# untitled.net
KiCad netlist of a schematic drawn in EAGLE
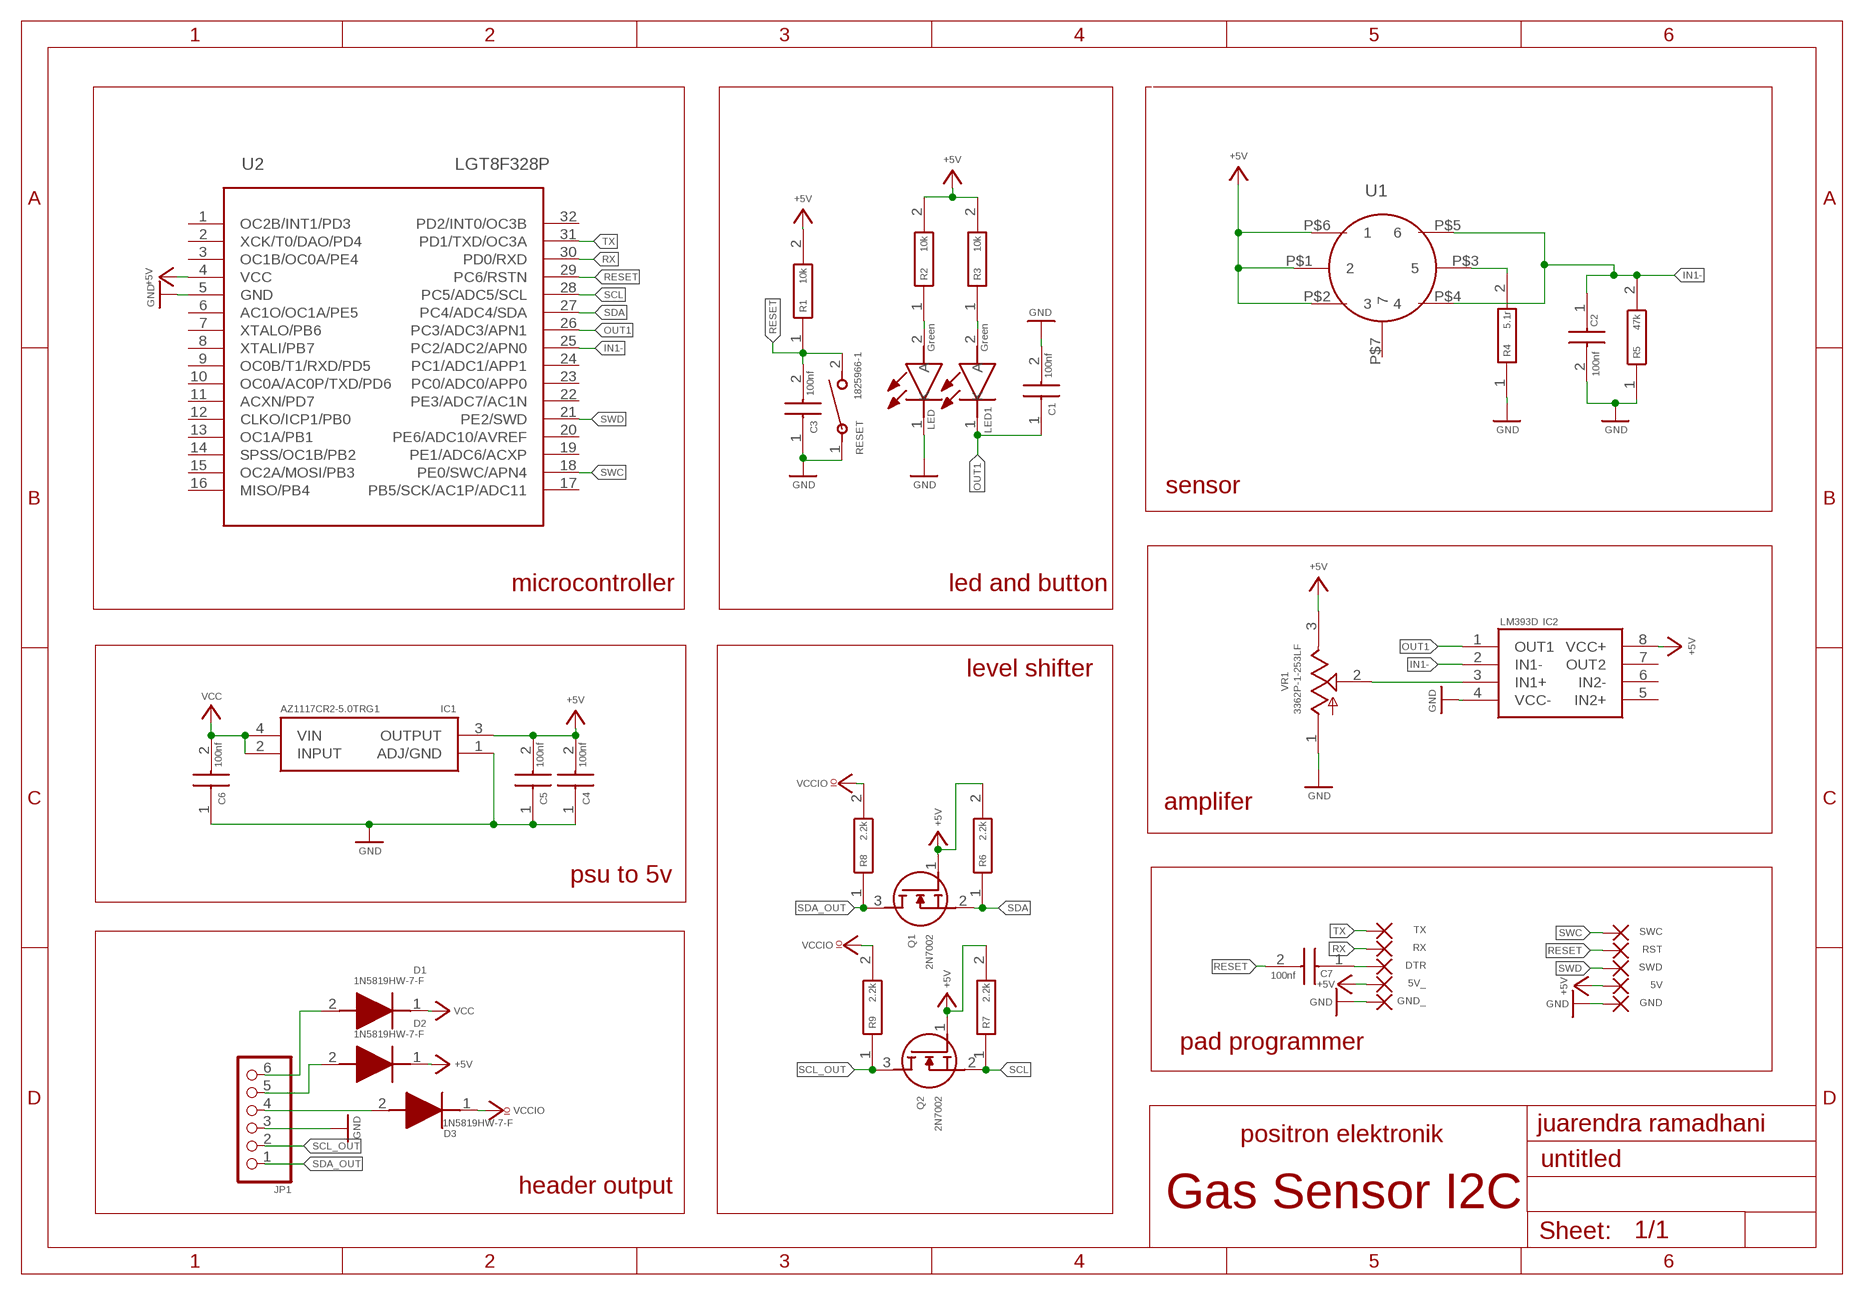
[diagram p0: schematic, sheet 1]

(export (version "E")
  (design (tool "Eeschema 10.0.6"))
  (components
    (comp (ref "5V")
      (value "SMD2")
      (footprint "eagle-import:SMD1,27-2,54")
      (libsource (lib "eagle-import") (part "SMD2"))
    )
    (comp (ref "5V_")
      (value "SMD2")
      (footprint "eagle-import:SMD1,27-2,54")
      (libsource (lib "eagle-import") (part "SMD2"))
    )
    (comp (ref "C1")
      (value "100nf")
      (footprint "eagle-import:CAPC1608X90N")
      (fields
        (field (name "MANUFACTURER_PART_NUMBER") "CGA3E3X7S2A104M080AB")
        (field (name "MOUSER_PART_NUMBER") "810-CGA3E3X7S2A104AB")
      )
      (libsource (lib "eagle-import") (part "CGA3E3X7S2A104M080AB"))
    )
    (comp (ref "C2")
      (value "100nf")
      (footprint "eagle-import:CAPC1608X90N")
      (fields
        (field (name "MANUFACTURER_PART_NUMBER") "CGA3E3X7S2A104M080AB")
        (field (name "MOUSER_PART_NUMBER") "810-CGA3E3X7S2A104AB")
      )
      (libsource (lib "eagle-import") (part "CGA3E3X7S2A104M080AB"))
    )
    (comp (ref "C3")
      (value "100nf")
      (footprint "eagle-import:CAPC1608X90N")
      (fields
        (field (name "MANUFACTURER_PART_NUMBER") "CGA3E3X7S2A104M080AB")
        (field (name "MOUSER_PART_NUMBER") "810-CGA3E3X7S2A104AB")
      )
      (libsource (lib "eagle-import") (part "CGA3E3X7S2A104M080AB"))
    )
    (comp (ref "C4")
      (value "100nf")
      (footprint "eagle-import:CAPC1608X90N")
      (fields
        (field (name "MANUFACTURER_PART_NUMBER") "CGA3E3X7S2A104M080AB")
        (field (name "MOUSER_PART_NUMBER") "810-CGA3E3X7S2A104AB")
      )
      (libsource (lib "eagle-import") (part "CGA3E3X7S2A104M080AB"))
    )
    (comp (ref "C5")
      (value "100nf")
      (footprint "eagle-import:CAPC1608X90N")
      (fields
        (field (name "MANUFACTURER_PART_NUMBER") "CGA3E3X7S2A104M080AB")
        (field (name "MOUSER_PART_NUMBER") "810-CGA3E3X7S2A104AB")
      )
      (libsource (lib "eagle-import") (part "CGA3E3X7S2A104M080AB"))
    )
    (comp (ref "C6")
      (value "100nf")
      (footprint "eagle-import:CAPC1608X90N")
      (fields
        (field (name "MANUFACTURER_PART_NUMBER") "CGA3E3X7S2A104M080AB")
        (field (name "MOUSER_PART_NUMBER") "810-CGA3E3X7S2A104AB")
      )
      (libsource (lib "eagle-import") (part "CGA3E3X7S2A104M080AB"))
    )
    (comp (ref "C7")
      (value "100nf")
      (footprint "eagle-import:CAPC1608X90N")
      (fields
        (field (name "MANUFACTURER_PART_NUMBER") "CGA3E3X7S2A104M080AB")
        (field (name "MOUSER_PART_NUMBER") "810-CGA3E3X7S2A104AB")
      )
      (libsource (lib "eagle-import") (part "CGA3E3X7S2A104M080AB"))
    )
    (comp (ref "D1")
      (value "1N5819HW-7-F")
      (footprint "eagle-import:SOD3716X145N")
      (fields (field (name "MOUSER_PART_NUMBER") "621-1N5819HW-F"))
      (libsource (lib "eagle-import") (part "1N5819HW-7-F"))
    )
    (comp (ref "D2")
      (value "1N5819HW-7-F")
      (footprint "eagle-import:SOD3716X145N")
      (fields (field (name "MOUSER_PART_NUMBER") "621-1N5819HW-F"))
      (libsource (lib "eagle-import") (part "1N5819HW-7-F"))
    )
    (comp (ref "D3")
      (value "1N5819HW-7-F")
      (footprint "eagle-import:SOD3716X145N")
      (fields (field (name "MOUSER_PART_NUMBER") "621-1N5819HW-F"))
      (libsource (lib "eagle-import") (part "1N5819HW-7-F"))
    )
    (comp (ref "DTR")
      (value "SMD2")
      (footprint "eagle-import:SMD1,27-2,54")
      (libsource (lib "eagle-import") (part "SMD2"))
    )
    (comp (ref "GND")
      (value "SMD2")
      (footprint "eagle-import:SMD1,27-2,54")
      (libsource (lib "eagle-import") (part "SMD2"))
    )
    (comp (ref "GND_")
      (value "SMD2")
      (footprint "eagle-import:SMD1,27-2,54")
      (libsource (lib "eagle-import") (part "SMD2"))
    )
    (comp (ref "IC1")
      (value "AZ1117CR2-5.0TRG1")
      (footprint "eagle-import:AP738133Y13")
      (fields (field (name "MOUSER_PART_NUMBER") "621-AZ1117CR25.0TRG1"))
      (libsource (lib "eagle-import") (part "AZ1117CR2-5.0TRG1"))
    )
    (comp (ref "IC2")
      (value "LM393D")
      (footprint "eagle-import:SOIC127P600X175-8N")
      (fields (field (name "MOUSER_PART_NUMBER") "511-LM393D"))
      (libsource (lib "eagle-import") (part "LM393D"))
    )
    (comp (ref "JP1")
      (value "PINHD-1X6")
      (footprint "eagle-import:1X06")
      (libsource (lib "eagle-import") (part "PINHD-1X6"))
    )
    (comp (ref "LED")
      (value "Green")
      (footprint "eagle-import:LEDC2012X80N")
      (fields
        (field (name "MANUFACTURER_PART_NUMBER") "150080BS75000")
        (field (name "MOUSER_PART_NUMBER") "710-150080BS75000")
      )
      (libsource (lib "eagle-import") (part "150080BS75000"))
    )
    (comp (ref "LED1")
      (value "Green")
      (footprint "eagle-import:LEDC2012X80N")
      (fields
        (field (name "MANUFACTURER_PART_NUMBER") "150080BS75000")
        (field (name "MOUSER_PART_NUMBER") "710-150080BS75000")
      )
      (libsource (lib "eagle-import") (part "150080BS75000"))
    )
    (comp (ref "Q1")
      (value "2N7002")
      (footprint "eagle-import:SOT95P280X125-3N")
      (fields (field (name "MOUSER_PART_NUMBER") "511-2N7002"))
      (libsource (lib "eagle-import") (part "2N7002"))
    )
    (comp (ref "Q2")
      (value "2N7002")
      (footprint "eagle-import:SOT95P280X125-3N")
      (fields (field (name "MOUSER_PART_NUMBER") "511-2N7002"))
      (libsource (lib "eagle-import") (part "2N7002"))
    )
    (comp (ref "R1")
      (value "10k")
      (footprint "eagle-import:RESC1608X50N")
      (fields
        (field (name "MANUFACTURER_PART_NUMBER") "CRCW060310K0FKEI")
        (field (name "MOUSER_PART_NUMBER") "71-CRCW060310K0FKEI")
      )
      (libsource (lib "eagle-import") (part "CRCW060310K0FKEI"))
    )
    (comp (ref "R2")
      (value "10k")
      (footprint "eagle-import:RESC1608X50N")
      (fields
        (field (name "MANUFACTURER_PART_NUMBER") "CRCW060310K0FKEI")
        (field (name "MOUSER_PART_NUMBER") "71-CRCW060310K0FKEI")
      )
      (libsource (lib "eagle-import") (part "CRCW060310K0FKEI"))
    )
    (comp (ref "R3")
      (value "10k")
      (footprint "eagle-import:RESC1608X50N")
      (fields
        (field (name "MANUFACTURER_PART_NUMBER") "CRCW060310K0FKEI")
        (field (name "MOUSER_PART_NUMBER") "71-CRCW060310K0FKEI")
      )
      (libsource (lib "eagle-import") (part "CRCW060310K0FKEI"))
    )
    (comp (ref "R4")
      (value "5.1r")
      (footprint "eagle-import:RESC1608X55N")
      (fields (field (name "MANUFACTURER_PART_NUMBER") "RT0603DRE075R1L"))
      (libsource (lib "eagle-import") (part "RT0603DRE075R1L"))
    )
    (comp (ref "R5")
      (value "47k")
      (footprint "eagle-import:RESC1608X55N")
      (fields (field (name "MANUFACTURER_PART_NUMBER") "AC0603FR-7W47KL"))
      (libsource (lib "eagle-import") (part "AC0603FR-7W47KL"))
    )
    (comp (ref "R6")
      (value "2.2k")
      (footprint "eagle-import:RESC1608X55N")
      (fields
        (field (name "MANUFACTURER_PART_NUMBER") "CR0603-FX-2201ELF")
        (field (name "MOUSER_PART_NUMBER") "652-CR0603FX-2201ELF")
      )
      (libsource (lib "eagle-import") (part "CR0603-FX-2201ELF"))
    )
    (comp (ref "R7")
      (value "2.2k")
      (footprint "eagle-import:RESC1608X55N")
      (fields
        (field (name "MANUFACTURER_PART_NUMBER") "CR0603-FX-2201ELF")
        (field (name "MOUSER_PART_NUMBER") "652-CR0603FX-2201ELF")
      )
      (libsource (lib "eagle-import") (part "CR0603-FX-2201ELF"))
    )
    (comp (ref "R8")
      (value "2.2k")
      (footprint "eagle-import:RESC1608X55N")
      (fields
        (field (name "MANUFACTURER_PART_NUMBER") "CR0603-FX-2201ELF")
        (field (name "MOUSER_PART_NUMBER") "652-CR0603FX-2201ELF")
      )
      (libsource (lib "eagle-import") (part "CR0603-FX-2201ELF"))
    )
    (comp (ref "R9")
      (value "2.2k")
      (footprint "eagle-import:RESC1608X55N")
      (fields
        (field (name "MANUFACTURER_PART_NUMBER") "CR0603-FX-2201ELF")
        (field (name "MOUSER_PART_NUMBER") "652-CR0603FX-2201ELF")
      )
      (libsource (lib "eagle-import") (part "CR0603-FX-2201ELF"))
    )
    (comp (ref "RESET")
      (value "1825966-1")
      (footprint "eagle-import:SWDIP2_256X170P100")
      (fields (field (name "COPYRIGHT") "Copyright (C) 2016 Accelerated Designs. All rights reserved"))
      (libsource (lib "eagle-import") (part "1825966-1"))
    )
    (comp (ref "RST")
      (value "SMD2")
      (footprint "eagle-import:SMD1,27-2,54")
      (libsource (lib "eagle-import") (part "SMD2"))
    )
    (comp (ref "RX")
      (value "SMD2")
      (footprint "eagle-import:SMD1,27-2,54")
      (libsource (lib "eagle-import") (part "SMD2"))
    )
    (comp (ref "SWC")
      (value "SMD2")
      (footprint "eagle-import:SMD1,27-2,54")
      (libsource (lib "eagle-import") (part "SMD2"))
    )
    (comp (ref "SWD")
      (value "SMD2")
      (footprint "eagle-import:SMD1,27-2,54")
      (libsource (lib "eagle-import") (part "SMD2"))
    )
    (comp (ref "TX")
      (value "SMD2")
      (footprint "eagle-import:SMD1,27-2,54")
      (libsource (lib "eagle-import") (part "SMD2"))
    )
    (comp (ref "U1")
      (value "MQ-SOCKET")
      (footprint "eagle-import:TQFP32-08")
      (libsource (lib "eagle-import") (part "MQ-SOCKET"))
    )
    (comp (ref "U2")
      (value "LGT8F328P")
      (footprint "eagle-import:TQFP32-08")
      (fields (field (name "MF") "Arduino"))
      (libsource (lib "eagle-import") (part "LGT8F328P"))
    )
    (comp (ref "VR1")
      (value "3362P-1-253LF")
      (footprint "eagle-import:TRIM_3362P-1-253LF")
      (fields (field (name "MF") "Bourns"))
      (libsource (lib "eagle-import") (part "3362P-1-253LF"))
    )
  )
  (nets
    (net (code "1") (name "+5V") (class "Default")
      (node (ref "5V") (pin "1") (pinfunction "P_1") (pintype "passive"))
      (node (ref "5V_") (pin "1") (pinfunction "P_1") (pintype "passive"))
      (node (ref "C4") (pin "2") (pinfunction "2_2") (pintype "bidirectional"))
      (node (ref "C5") (pin "2") (pinfunction "2_2") (pintype "bidirectional"))
      (node (ref "D2") (pin "1") (pinfunction "K_1") (pintype "bidirectional"))
      (node (ref "IC1") (pin "3") (pinfunction "OUTPUT_3") (pintype "bidirectional"))
      (node (ref "IC2") (pin "8") (pinfunction "VCC+_8") (pintype "bidirectional"))
      (node (ref "Q1") (pin "1") (pinfunction "G_1") (pintype "bidirectional"))
      (node (ref "Q2") (pin "1") (pinfunction "G_1") (pintype "bidirectional"))
      (node (ref "R1") (pin "2") (pinfunction "2_2") (pintype "bidirectional"))
      (node (ref "R2") (pin "2") (pinfunction "2_2") (pintype "bidirectional"))
      (node (ref "R3") (pin "2") (pinfunction "2_2") (pintype "bidirectional"))
      (node (ref "R6") (pin "2") (pinfunction "2_2") (pintype "bidirectional"))
      (node (ref "R7") (pin "2") (pinfunction "2_2") (pintype "bidirectional"))
      (node (ref "U1") (pin "P$1") (pinfunction "2_P$1") (pintype "bidirectional"))
      (node (ref "U1") (pin "P$2") (pinfunction "3_P$2") (pintype "bidirectional"))
      (node (ref "U1") (pin "P$6") (pinfunction "1_P$6") (pintype "bidirectional"))
      (node (ref "U2") (pin "4") (pinfunction "VCC_4") (pintype "power_in"))
      (node (ref "VR1") (pin "3") (pinfunction "CW_3") (pintype "passive"))
    )
    (net (code "2") (name "GND") (class "Default")
      (node (ref "C1") (pin "2") (pinfunction "2_2") (pintype "bidirectional"))
      (node (ref "C2") (pin "2") (pinfunction "2_2") (pintype "bidirectional"))
      (node (ref "C3") (pin "1") (pinfunction "1_1") (pintype "bidirectional"))
      (node (ref "C4") (pin "1") (pinfunction "1_1") (pintype "bidirectional"))
      (node (ref "C5") (pin "1") (pinfunction "1_1") (pintype "bidirectional"))
      (node (ref "C6") (pin "1") (pinfunction "1_1") (pintype "bidirectional"))
      (node (ref "GND") (pin "1") (pinfunction "P_1") (pintype "passive"))
      (node (ref "GND_") (pin "1") (pinfunction "P_1") (pintype "passive"))
      (node (ref "IC1") (pin "1") (pinfunction "ADJ/GND_1") (pintype "bidirectional"))
      (node (ref "IC2") (pin "4") (pinfunction "VCC-_4") (pintype "bidirectional"))
      (node (ref "JP1") (pin "3") (pinfunction "3_3") (pintype "passive"))
      (node (ref "LED") (pin "1") (pinfunction "K_1") (pintype "bidirectional"))
      (node (ref "R4") (pin "1") (pinfunction "1_1") (pintype "bidirectional"))
      (node (ref "R5") (pin "1") (pinfunction "1_1") (pintype "bidirectional"))
      (node (ref "RESET") (pin "1") (pinfunction "1_1") (pintype "passive"))
      (node (ref "U2") (pin "5") (pinfunction "GND_5") (pintype "power_in"))
      (node (ref "VR1") (pin "1") (pinfunction "CCW_1") (pintype "passive"))
    )
    (net (code "3") (name "IN1-") (class "Default")
      (node (ref "C2") (pin "1") (pinfunction "1_1") (pintype "bidirectional"))
      (node (ref "IC2") (pin "2") (pinfunction "IN1-_2") (pintype "bidirectional"))
      (node (ref "R5") (pin "2") (pinfunction "2_2") (pintype "bidirectional"))
      (node (ref "U1") (pin "P$4") (pinfunction "4_P$4") (pintype "bidirectional"))
      (node (ref "U1") (pin "P$5") (pinfunction "6_P$5") (pintype "bidirectional"))
      (node (ref "U2") (pin "25") (pinfunction "PC2/ADC2/APN0_25") (pintype "bidirectional"))
    )
    (net (code "4") (name "Net-(D1-A)") (class "Default")
      (node (ref "D1") (pin "2") (pinfunction "A_2") (pintype "bidirectional"))
      (node (ref "JP1") (pin "6") (pinfunction "6_6") (pintype "passive"))
    )
    (net (code "5") (name "Net-(D2-A)") (class "Default")
      (node (ref "D2") (pin "2") (pinfunction "A_2") (pintype "bidirectional"))
      (node (ref "JP1") (pin "5") (pinfunction "5_5") (pintype "passive"))
    )
    (net (code "6") (name "Net-(D3-A)") (class "Default")
      (node (ref "D3") (pin "2") (pinfunction "A_2") (pintype "bidirectional"))
      (node (ref "JP1") (pin "4") (pinfunction "4_4") (pintype "passive"))
    )
    (net (code "7") (name "Net-(DTR-P)") (class "Default")
      (node (ref "C7") (pin "1") (pinfunction "1_1") (pintype "bidirectional"))
      (node (ref "DTR") (pin "1") (pinfunction "P_1") (pintype "passive"))
    )
    (net (code "8") (name "Net-(IC2-IN1+)") (class "Default")
      (node (ref "IC2") (pin "3") (pinfunction "IN1+_3") (pintype "bidirectional"))
      (node (ref "VR1") (pin "2") (pinfunction "WIPER_2") (pintype "passive"))
    )
    (net (code "9") (name "Net-(LED-A)") (class "Default")
      (node (ref "LED") (pin "2") (pinfunction "A_2") (pintype "bidirectional"))
      (node (ref "R2") (pin "1") (pinfunction "1_1") (pintype "bidirectional"))
    )
    (net (code "10") (name "Net-(LED1-A)") (class "Default")
      (node (ref "LED1") (pin "2") (pinfunction "A_2") (pintype "bidirectional"))
      (node (ref "R3") (pin "1") (pinfunction "1_1") (pintype "bidirectional"))
    )
    (net (code "11") (name "Net-(U1-5)") (class "Default")
      (node (ref "R4") (pin "2") (pinfunction "2_2") (pintype "bidirectional"))
      (node (ref "U1") (pin "P$3") (pinfunction "5_P$3") (pintype "bidirectional"))
    )
    (net (code "12") (name "OUT1") (class "Default")
      (node (ref "C1") (pin "1") (pinfunction "1_1") (pintype "bidirectional"))
      (node (ref "IC2") (pin "1") (pinfunction "OUT1_1") (pintype "bidirectional"))
      (node (ref "LED1") (pin "1") (pinfunction "K_1") (pintype "bidirectional"))
      (node (ref "U2") (pin "26") (pinfunction "PC3/ADC3/APN1_26") (pintype "bidirectional"))
    )
    (net (code "13") (name "RESET") (class "Default")
      (node (ref "C3") (pin "2") (pinfunction "2_2") (pintype "bidirectional"))
      (node (ref "C7") (pin "2") (pinfunction "2_2") (pintype "bidirectional"))
      (node (ref "R1") (pin "1") (pinfunction "1_1") (pintype "bidirectional"))
      (node (ref "RESET") (pin "2") (pinfunction "2_2") (pintype "passive"))
      (node (ref "RST") (pin "1") (pinfunction "P_1") (pintype "passive"))
      (node (ref "U2") (pin "29") (pinfunction "PC6/RSTN_29") (pintype "bidirectional"))
    )
    (net (code "14") (name "RX") (class "Default")
      (node (ref "RX") (pin "1") (pinfunction "P_1") (pintype "passive"))
      (node (ref "U2") (pin "30") (pinfunction "PD0/RXD_30") (pintype "bidirectional"))
    )
    (net (code "15") (name "SCL") (class "Default")
      (node (ref "Q2") (pin "2") (pinfunction "S_2") (pintype "bidirectional"))
      (node (ref "R7") (pin "1") (pinfunction "1_1") (pintype "bidirectional"))
      (node (ref "U2") (pin "28") (pinfunction "PC5/ADC5/SCL_28") (pintype "bidirectional"))
    )
    (net (code "16") (name "SCL_OUT") (class "Default")
      (node (ref "JP1") (pin "2") (pinfunction "2_2") (pintype "passive"))
      (node (ref "Q2") (pin "3") (pinfunction "D_3") (pintype "bidirectional"))
      (node (ref "R9") (pin "1") (pinfunction "1_1") (pintype "bidirectional"))
    )
    (net (code "17") (name "SDA") (class "Default")
      (node (ref "Q1") (pin "2") (pinfunction "S_2") (pintype "bidirectional"))
      (node (ref "R6") (pin "1") (pinfunction "1_1") (pintype "bidirectional"))
      (node (ref "U2") (pin "27") (pinfunction "PC4/ADC4/SDA_27") (pintype "bidirectional"))
    )
    (net (code "18") (name "SDA_OUT") (class "Default")
      (node (ref "JP1") (pin "1") (pinfunction "1_1") (pintype "passive"))
      (node (ref "Q1") (pin "3") (pinfunction "D_3") (pintype "bidirectional"))
      (node (ref "R8") (pin "1") (pinfunction "1_1") (pintype "bidirectional"))
    )
    (net (code "19") (name "SWC") (class "Default")
      (node (ref "SWC") (pin "1") (pinfunction "P_1") (pintype "passive"))
      (node (ref "U2") (pin "18") (pinfunction "PE0/SWC/APN4_18") (pintype "bidirectional"))
    )
    (net (code "20") (name "SWD") (class "Default")
      (node (ref "SWD") (pin "1") (pinfunction "P_1") (pintype "passive"))
      (node (ref "U2") (pin "21") (pinfunction "PE2/SWD_21") (pintype "bidirectional"))
    )
    (net (code "21") (name "TX") (class "Default")
      (node (ref "TX") (pin "1") (pinfunction "P_1") (pintype "passive"))
      (node (ref "U2") (pin "31") (pinfunction "PD1/TXD/OC3A_31") (pintype "bidirectional"))
    )
    (net (code "22") (name "VCC") (class "Default")
      (node (ref "C6") (pin "2") (pinfunction "2_2") (pintype "bidirectional"))
      (node (ref "D1") (pin "1") (pinfunction "K_1") (pintype "bidirectional"))
      (node (ref "IC1") (pin "2") (pinfunction "INPUT_2") (pintype "bidirectional"))
      (node (ref "IC1") (pin "4") (pinfunction "VIN_4") (pintype "bidirectional"))
    )
    (net (code "23") (name "VCCIO") (class "Default")
      (node (ref "D3") (pin "1") (pinfunction "K_1") (pintype "bidirectional"))
      (node (ref "R8") (pin "2") (pinfunction "2_2") (pintype "bidirectional"))
      (node (ref "R9") (pin "2") (pinfunction "2_2") (pintype "bidirectional"))
    )
    (net (code "24") (name "unconnected-(IC2-IN2+-Pad5)") (class "Default")
      (node (ref "IC2") (pin "5") (pinfunction "IN2+_5") (pintype "bidirectional"))
    )
    (net (code "25") (name "unconnected-(IC2-IN2--Pad6)") (class "Default")
      (node (ref "IC2") (pin "6") (pinfunction "IN2-_6") (pintype "bidirectional"))
    )
    (net (code "26") (name "unconnected-(IC2-OUT2-Pad7)") (class "Default")
      (node (ref "IC2") (pin "7") (pinfunction "OUT2_7") (pintype "bidirectional"))
    )
    (net (code "27") (name "unconnected-(U1-7-PadP$7)") (class "Default")
      (node (ref "U1") (pin "P$7") (pinfunction "7_P$7") (pintype "bidirectional"))
    )
    (net (code "28") (name "unconnected-(U2-AC1O{slash}OC1A{slash}PE5-Pad6)") (class "Default")
      (node (ref "U2") (pin "6") (pinfunction "AC1O/OC1A/PE5_6") (pintype "bidirectional"))
    )
    (net (code "29") (name "unconnected-(U2-ACXN{slash}PD7-Pad11)") (class "Default")
      (node (ref "U2") (pin "11") (pinfunction "ACXN/PD7_11") (pintype "bidirectional"))
    )
    (net (code "30") (name "unconnected-(U2-CLKO{slash}ICP1{slash}PB0-Pad12)") (class "Default")
      (node (ref "U2") (pin "12") (pinfunction "CLKO/ICP1/PB0_12") (pintype "bidirectional"))
    )
    (net (code "31") (name "unconnected-(U2-MISO{slash}PB4-Pad16)") (class "Default")
      (node (ref "U2") (pin "16") (pinfunction "MISO/PB4_16") (pintype "bidirectional"))
    )
    (net (code "32") (name "unconnected-(U2-OC0A{slash}AC0P{slash}TXD{slash}PD6-Pad10)") (class "Default")
      (node (ref "U2") (pin "10") (pinfunction "OC0A/AC0P/TXD/PD6_10") (pintype "bidirectional"))
    )
    (net (code "33") (name "unconnected-(U2-OC0B{slash}T1{slash}RXD{slash}PD5-Pad9)") (class "Default")
      (node (ref "U2") (pin "9") (pinfunction "OC0B/T1/RXD/PD5_9") (pintype "bidirectional"))
    )
    (net (code "34") (name "unconnected-(U2-OC1A{slash}PB1-Pad13)") (class "Default")
      (node (ref "U2") (pin "13") (pinfunction "OC1A/PB1_13") (pintype "bidirectional"))
    )
    (net (code "35") (name "unconnected-(U2-OC1B{slash}OC0A{slash}PE4-Pad3)") (class "Default")
      (node (ref "U2") (pin "3") (pinfunction "OC1B/OC0A/PE4_3") (pintype "bidirectional"))
    )
    (net (code "36") (name "unconnected-(U2-OC2A{slash}MOSI{slash}PB3-Pad15)") (class "Default")
      (node (ref "U2") (pin "15") (pinfunction "OC2A/MOSI/PB3_15") (pintype "bidirectional"))
    )
    (net (code "37") (name "unconnected-(U2-OC2B{slash}INT1{slash}PD3-Pad1)") (class "Default")
      (node (ref "U2") (pin "1") (pinfunction "OC2B/INT1/PD3_1") (pintype "bidirectional"))
    )
    (net (code "38") (name "unconnected-(U2-PB5{slash}SCK{slash}AC1P{slash}ADC11-Pad17)") (class "Default")
      (node (ref "U2") (pin "17") (pinfunction "PB5/SCK/AC1P/ADC11_17") (pintype "bidirectional"))
    )
    (net (code "39") (name "unconnected-(U2-PC0{slash}ADC0{slash}APP0-Pad23)") (class "Default")
      (node (ref "U2") (pin "23") (pinfunction "PC0/ADC0/APP0_23") (pintype "bidirectional"))
    )
    (net (code "40") (name "unconnected-(U2-PC1{slash}ADC1{slash}APP1-Pad24)") (class "Default")
      (node (ref "U2") (pin "24") (pinfunction "PC1/ADC1/APP1_24") (pintype "bidirectional"))
    )
    (net (code "41") (name "unconnected-(U2-PD2{slash}INT0{slash}OC3B-Pad32)") (class "Default")
      (node (ref "U2") (pin "32") (pinfunction "PD2/INT0/OC3B_32") (pintype "bidirectional"))
    )
    (net (code "42") (name "unconnected-(U2-PE1{slash}ADC6{slash}ACXP-Pad19)") (class "Default")
      (node (ref "U2") (pin "19") (pinfunction "PE1/ADC6/ACXP_19") (pintype "bidirectional"))
    )
    (net (code "43") (name "unconnected-(U2-PE3{slash}ADC7{slash}AC1N-Pad22)") (class "Default")
      (node (ref "U2") (pin "22") (pinfunction "PE3/ADC7/AC1N_22") (pintype "bidirectional"))
    )
    (net (code "44") (name "unconnected-(U2-PE6{slash}ADC10{slash}AVREF-Pad20)") (class "Default")
      (node (ref "U2") (pin "20") (pinfunction "PE6/ADC10/AVREF_20") (pintype "bidirectional"))
    )
    (net (code "45") (name "unconnected-(U2-SPSS{slash}OC1B{slash}PB2-Pad14)") (class "Default")
      (node (ref "U2") (pin "14") (pinfunction "SPSS/OC1B/PB2_14") (pintype "bidirectional"))
    )
    (net (code "46") (name "unconnected-(U2-XCK{slash}T0{slash}DAO{slash}PD4-Pad2)") (class "Default")
      (node (ref "U2") (pin "2") (pinfunction "XCK/T0/DAO/PD4_2") (pintype "bidirectional"))
    )
    (net (code "47") (name "unconnected-(U2-XTALI{slash}PB7-Pad8)") (class "Default")
      (node (ref "U2") (pin "8") (pinfunction "XTALI/PB7_8") (pintype "bidirectional"))
    )
    (net (code "48") (name "unconnected-(U2-XTALO{slash}PB6-Pad7)") (class "Default")
      (node (ref "U2") (pin "7") (pinfunction "XTALO/PB6_7") (pintype "bidirectional"))
    )
  )
)
